# peripheral_PWM.net
KiCad netlist of a schematic drawn in Altium Designer
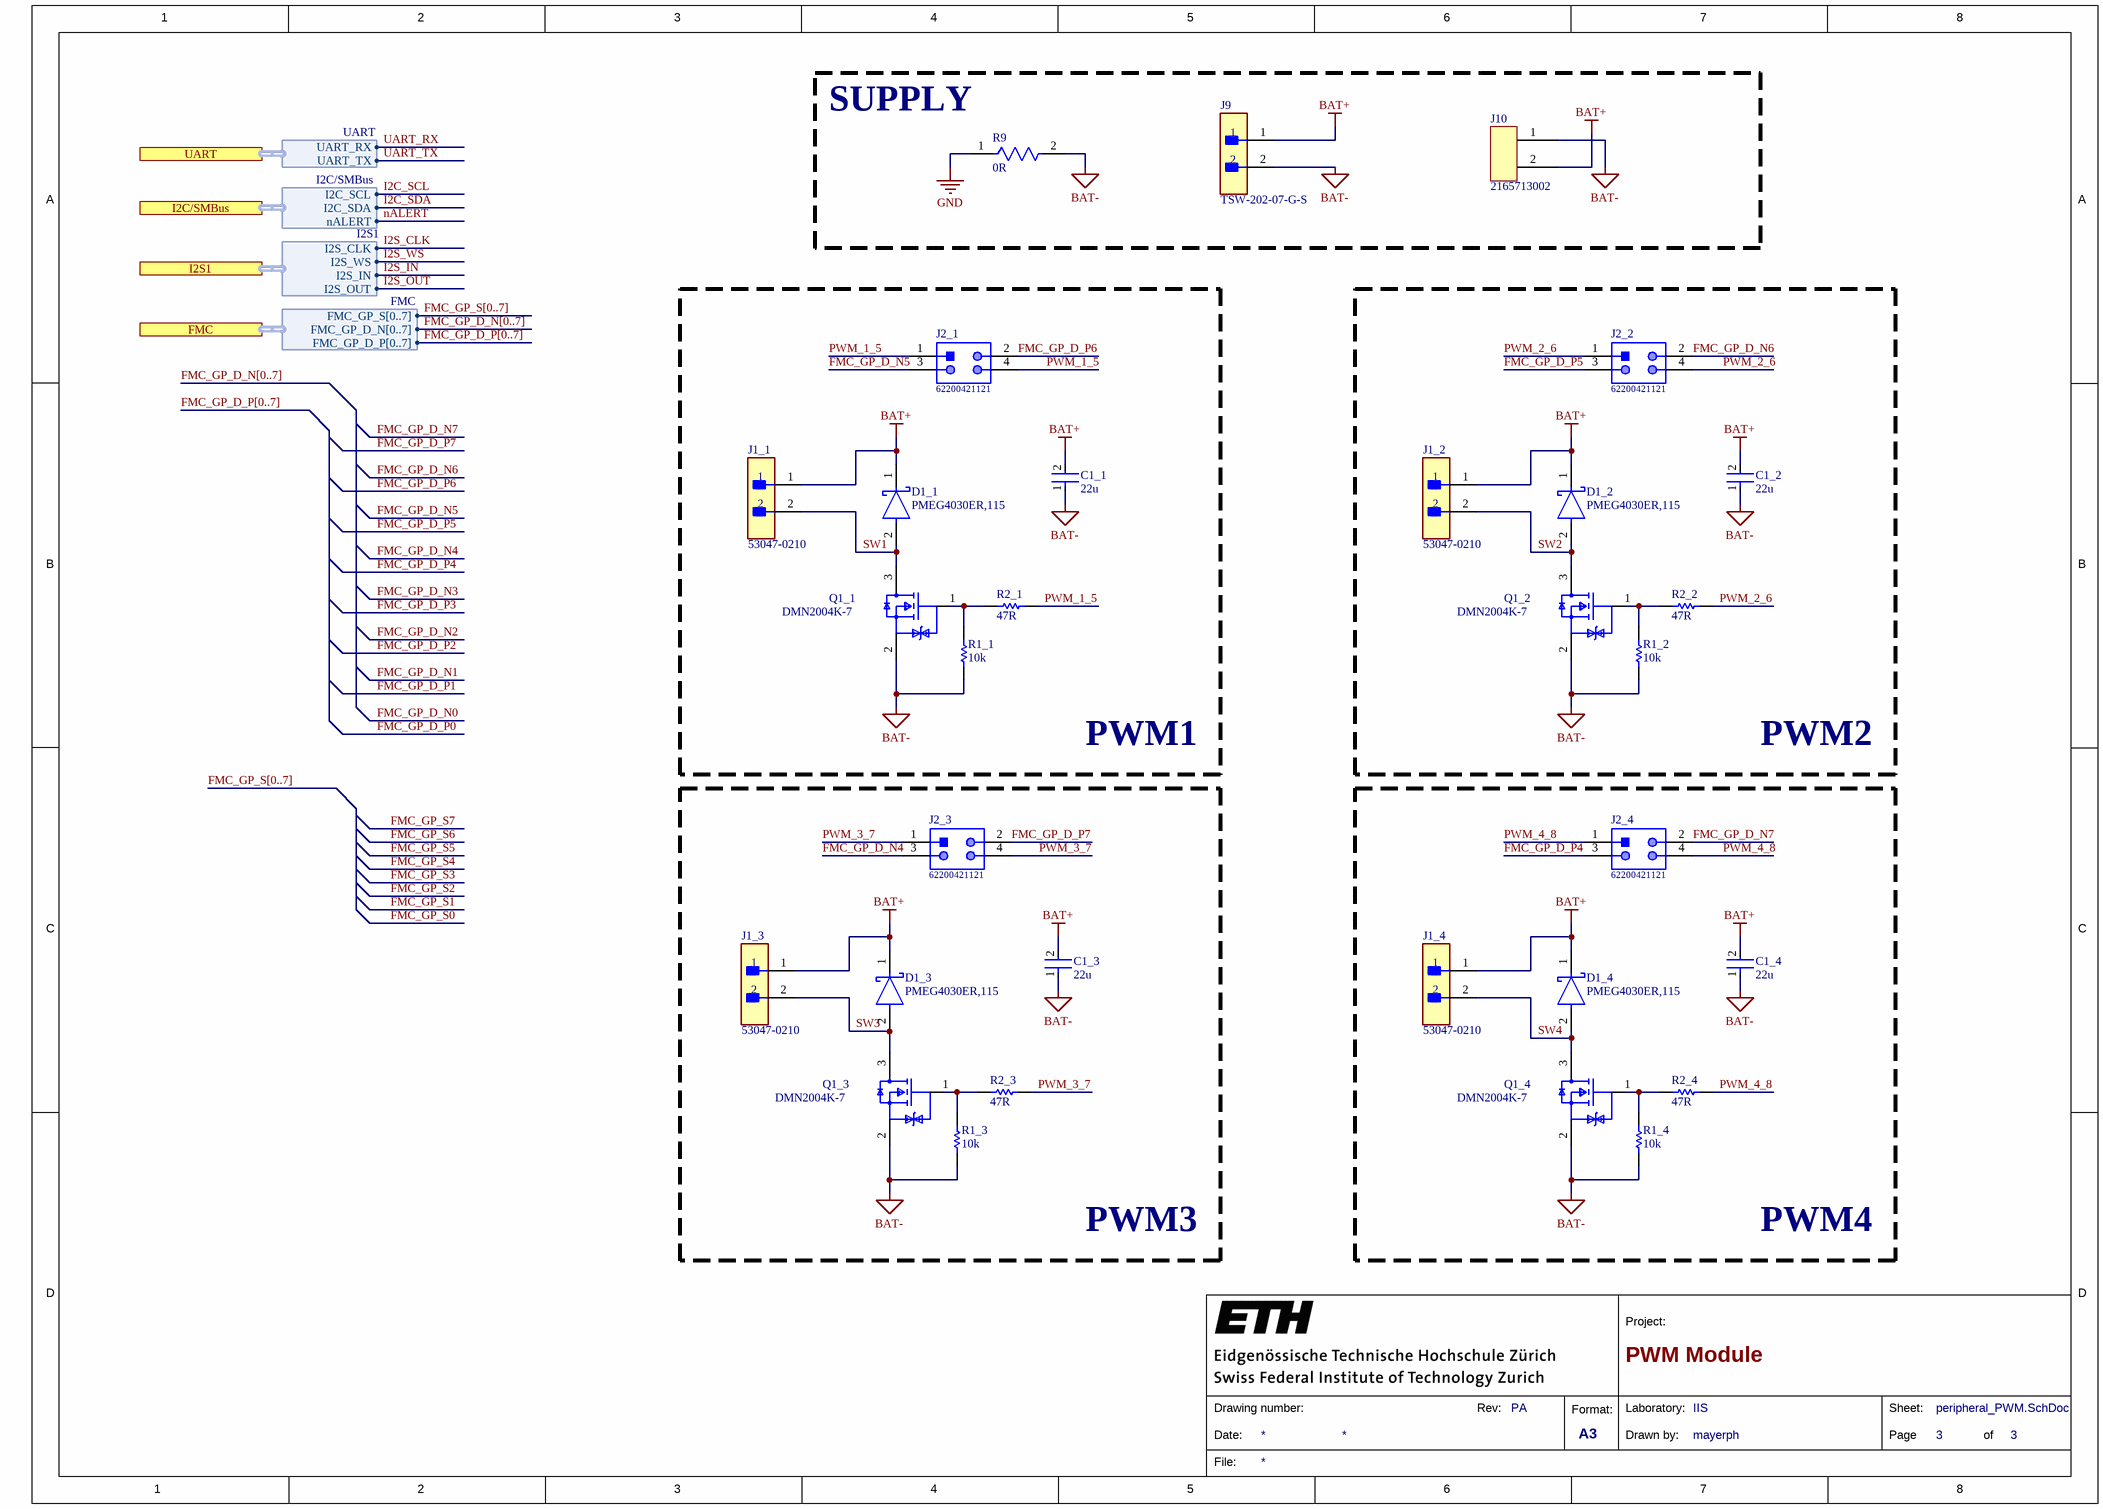
[diagram p0: peripheral_PWM.SchDoc]

(export (version "E")
  (design (tool "Eeschema 10.0.6"))
  (components
    (comp (ref "C1_1")
      (value "22u")
      (footprint "FP-CL10-IPC_B")
      (description "Cap Ceramic 22uF 16V X5R ±20% Pad SMD 0603 +85°C T/R")
      (fields (field (name "TOLERANCE") "20%") (field (name "MANUFACTURER") "Samsung"))
      (libsource (lib "Altium Content Vault") (part "b4654b650e69147ec39a6b967a45e02"))
    )
    (comp (ref "C1_2")
      (value "22u")
      (footprint "FP-CL10-IPC_B")
      (description "Cap Ceramic 22uF 16V X5R ±20% Pad SMD 0603 +85°C T/R")
      (fields (field (name "TOLERANCE") "20%") (field (name "MANUFACTURER") "Samsung"))
      (libsource (lib "Altium Content Vault") (part "b4654b650e69147ec39a6b967a45e02"))
    )
    (comp (ref "C1_3")
      (value "22u")
      (footprint "FP-CL10-IPC_B")
      (description "Cap Ceramic 22uF 16V X5R ±20% Pad SMD 0603 +85°C T/R")
      (fields (field (name "TOLERANCE") "20%") (field (name "MANUFACTURER") "Samsung"))
      (libsource (lib "Altium Content Vault") (part "b4654b650e69147ec39a6b967a45e02"))
    )
    (comp (ref "C1_4")
      (value "22u")
      (footprint "FP-CL10-IPC_B")
      (description "Cap Ceramic 22uF 16V X5R ±20% Pad SMD 0603 +85°C T/R")
      (fields (field (name "TOLERANCE") "20%") (field (name "MANUFACTURER") "Samsung"))
      (libsource (lib "Altium Content Vault") (part "b4654b650e69147ec39a6b967a45e02"))
    )
    (comp (ref "D1_1")
      (value "PMEG4030ER,115")
      (footprint "FP-SOD123W-MFG")
      (description "DIODE SCHOTTKY 40V 3A SOD123W")
      (fields (field (name "MANUFACTURER") "Nexperia USA Inc."))
      (libsource (lib "Altium Content Vault") (part "e9b750318ede8d9850c058872da20e7"))
    )
    (comp (ref "D1_2")
      (value "PMEG4030ER,115")
      (footprint "FP-SOD123W-MFG")
      (description "DIODE SCHOTTKY 40V 3A SOD123W")
      (fields (field (name "MANUFACTURER") "Nexperia USA Inc."))
      (libsource (lib "Altium Content Vault") (part "e9b750318ede8d9850c058872da20e7"))
    )
    (comp (ref "D1_3")
      (value "PMEG4030ER,115")
      (footprint "FP-SOD123W-MFG")
      (description "DIODE SCHOTTKY 40V 3A SOD123W")
      (fields (field (name "MANUFACTURER") "Nexperia USA Inc."))
      (libsource (lib "Altium Content Vault") (part "e9b750318ede8d9850c058872da20e7"))
    )
    (comp (ref "D1_4")
      (value "PMEG4030ER,115")
      (footprint "FP-SOD123W-MFG")
      (description "DIODE SCHOTTKY 40V 3A SOD123W")
      (fields (field (name "MANUFACTURER") "Nexperia USA Inc."))
      (libsource (lib "Altium Content Vault") (part "e9b750318ede8d9850c058872da20e7"))
    )
    (comp (ref "J1_1")
      (value "53047-0210")
      (footprint "FP-53047-0210-MFG")
      (description "CONN HEADER VERT 2POS 1.25MM")
      (fields
        (field (name "OCTOPART") "https://octopart.com/53047-0210-molex-276772")
        (field (name "MANUFACTURER") "Molex")
      )
      (libsource (lib "Altium Content Vault") (part "3bc925449376181038e59eaffc5286c"))
    )
    (comp (ref "J1_2")
      (value "53047-0210")
      (footprint "FP-53047-0210-MFG")
      (description "CONN HEADER VERT 2POS 1.25MM")
      (fields
        (field (name "OCTOPART") "https://octopart.com/53047-0210-molex-276772")
        (field (name "MANUFACTURER") "Molex")
      )
      (libsource (lib "Altium Content Vault") (part "3bc925449376181038e59eaffc5286c"))
    )
    (comp (ref "J1_3")
      (value "53047-0210")
      (footprint "FP-53047-0210-MFG")
      (description "CONN HEADER VERT 2POS 1.25MM")
      (fields
        (field (name "OCTOPART") "https://octopart.com/53047-0210-molex-276772")
        (field (name "MANUFACTURER") "Molex")
      )
      (libsource (lib "Altium Content Vault") (part "3bc925449376181038e59eaffc5286c"))
    )
    (comp (ref "J1_4")
      (value "53047-0210")
      (footprint "FP-53047-0210-MFG")
      (description "CONN HEADER VERT 2POS 1.25MM")
      (fields
        (field (name "OCTOPART") "https://octopart.com/53047-0210-molex-276772")
        (field (name "MANUFACTURER") "Molex")
      )
      (libsource (lib "Altium Content Vault") (part "3bc925449376181038e59eaffc5286c"))
    )
    (comp (ref "J2_1")
      (value "62200421121")
      (footprint "62200421121")
      (description "THT Vertical Pin Header WR-PHD, Pitch 1.27 mm, Dual Row, 4 pins")
      (fields (field (name "MANUFACTURER") "Wurth Elektronik") (field (name "PUBLISHER") "WurthElektronik"))
      (libsource (lib "Altium Content Vault") (part "WE-CN-2P-M-R4"))
    )
    (comp (ref "J2_2")
      (value "62200421121")
      (footprint "62200421121")
      (description "THT Vertical Pin Header WR-PHD, Pitch 1.27 mm, Dual Row, 4 pins")
      (fields (field (name "MANUFACTURER") "Wurth Elektronik") (field (name "PUBLISHER") "WurthElektronik"))
      (libsource (lib "Altium Content Vault") (part "WE-CN-2P-M-R4"))
    )
    (comp (ref "J2_3")
      (value "62200421121")
      (footprint "62200421121")
      (description "THT Vertical Pin Header WR-PHD, Pitch 1.27 mm, Dual Row, 4 pins")
      (fields (field (name "MANUFACTURER") "Wurth Elektronik") (field (name "PUBLISHER") "WurthElektronik"))
      (libsource (lib "Altium Content Vault") (part "WE-CN-2P-M-R4"))
    )
    (comp (ref "J2_4")
      (value "62200421121")
      (footprint "62200421121")
      (description "THT Vertical Pin Header WR-PHD, Pitch 1.27 mm, Dual Row, 4 pins")
      (fields (field (name "MANUFACTURER") "Wurth Elektronik") (field (name "PUBLISHER") "WurthElektronik"))
      (libsource (lib "Altium Content Vault") (part "WE-CN-2P-M-R4"))
    )
    (comp (ref "J9")
      (value "TSW-202-07-G-S")
      (footprint "FP-TSW-202-07-G-S-MFG")
      (description "CONN HEADER VERT 2POS 5.08MM")
      (fields
        (field (name "MANUFACTURER") "Samtec")
        (field (name "OCTOPART") "https://octopart.com/tsw-202-07-g-s-samtec-13117432")
      )
      (libsource (lib "Altium Content Vault") (part "3bc925449376181038e59eaffc5286c"))
    )
    (comp (ref "J10")
      (value "2165713002")
      (footprint "PcbLib1:PCBComponent_1")
      (fields (field (name "MANUFACTURER") "Molex"))
      (libsource (lib "Schlib1") (part "2165713002"))
    )
    (comp (ref "Q1_1")
      (value "DMN2004K-7")
      (footprint "FP-SOT23-MFG")
      (description "MOSFET N-CH 20V 0.63A SOT23-3")
      (fields
        (field (name "OCTOPART") "https://octopart.com/dmn2004k-7-diodes+inc.-7127688")
        (field (name "MANUFACTURER") "Diodes Inc.")
      )
      (libsource (lib "Altium Content Vault") (part "6bf9a98fc5d989e2cd7172508213873"))
    )
    (comp (ref "Q1_2")
      (value "DMN2004K-7")
      (footprint "FP-SOT23-MFG")
      (description "MOSFET N-CH 20V 0.63A SOT23-3")
      (fields
        (field (name "OCTOPART") "https://octopart.com/dmn2004k-7-diodes+inc.-7127688")
        (field (name "MANUFACTURER") "Diodes Inc.")
      )
      (libsource (lib "Altium Content Vault") (part "6bf9a98fc5d989e2cd7172508213873"))
    )
    (comp (ref "Q1_3")
      (value "DMN2004K-7")
      (footprint "FP-SOT23-MFG")
      (description "MOSFET N-CH 20V 0.63A SOT23-3")
      (fields
        (field (name "OCTOPART") "https://octopart.com/dmn2004k-7-diodes+inc.-7127688")
        (field (name "MANUFACTURER") "Diodes Inc.")
      )
      (libsource (lib "Altium Content Vault") (part "6bf9a98fc5d989e2cd7172508213873"))
    )
    (comp (ref "Q1_4")
      (value "DMN2004K-7")
      (footprint "FP-SOT23-MFG")
      (description "MOSFET N-CH 20V 0.63A SOT23-3")
      (fields
        (field (name "OCTOPART") "https://octopart.com/dmn2004k-7-diodes+inc.-7127688")
        (field (name "MANUFACTURER") "Diodes Inc.")
      )
      (libsource (lib "Altium Content Vault") (part "6bf9a98fc5d989e2cd7172508213873"))
    )
    (comp (ref "R1_1")
      (value "10k")
      (footprint "RESC1609X55X30LL15T15")
      (description "Chip Resistor, 10 KOhm, +/- 1%, 0.1 W, -55 to 155 degC, 0603 (1608 Metric), RoHS, Tape and Reel")
      (fields (field (name "TOLERANCE") "1%") (field (name "MANUFACTURER") "Panasonic"))
      (libsource (lib "Altium Content Vault") (part "RES-2"))
    )
    (comp (ref "R1_2")
      (value "10k")
      (footprint "RESC1609X55X30LL15T15")
      (description "Chip Resistor, 10 KOhm, +/- 1%, 0.1 W, -55 to 155 degC, 0603 (1608 Metric), RoHS, Tape and Reel")
      (fields (field (name "TOLERANCE") "1%") (field (name "MANUFACTURER") "Panasonic"))
      (libsource (lib "Altium Content Vault") (part "RES-2"))
    )
    (comp (ref "R1_3")
      (value "10k")
      (footprint "RESC1609X55X30LL15T15")
      (description "Chip Resistor, 10 KOhm, +/- 1%, 0.1 W, -55 to 155 degC, 0603 (1608 Metric), RoHS, Tape and Reel")
      (fields (field (name "TOLERANCE") "1%") (field (name "MANUFACTURER") "Panasonic"))
      (libsource (lib "Altium Content Vault") (part "RES-2"))
    )
    (comp (ref "R1_4")
      (value "10k")
      (footprint "RESC1609X55X30LL15T15")
      (description "Chip Resistor, 10 KOhm, +/- 1%, 0.1 W, -55 to 155 degC, 0603 (1608 Metric), RoHS, Tape and Reel")
      (fields (field (name "TOLERANCE") "1%") (field (name "MANUFACTURER") "Panasonic"))
      (libsource (lib "Altium Content Vault") (part "RES-2"))
    )
    (comp (ref "R2_1")
      (value "47R")
      (footprint "RESC1608X55X30NL15T15")
      (description "Chip Resistor, 47 Ohm, +/- 1%, 0.1 W, -55 to 155 degC, 0603 (1608 Metric), RoHS, Tape and Reel")
      (fields (field (name "TOLERANCE") "1%") (field (name "MANUFACTURER") "Panasonic"))
      (libsource (lib "Altium Content Vault") (part "RES-2"))
    )
    (comp (ref "R2_2")
      (value "47R")
      (footprint "RESC1608X55X30NL15T15")
      (description "Chip Resistor, 47 Ohm, +/- 1%, 0.1 W, -55 to 155 degC, 0603 (1608 Metric), RoHS, Tape and Reel")
      (fields (field (name "TOLERANCE") "1%") (field (name "MANUFACTURER") "Panasonic"))
      (libsource (lib "Altium Content Vault") (part "RES-2"))
    )
    (comp (ref "R2_3")
      (value "47R")
      (footprint "RESC1608X55X30NL15T15")
      (description "Chip Resistor, 47 Ohm, +/- 1%, 0.1 W, -55 to 155 degC, 0603 (1608 Metric), RoHS, Tape and Reel")
      (fields (field (name "TOLERANCE") "1%") (field (name "MANUFACTURER") "Panasonic"))
      (libsource (lib "Altium Content Vault") (part "RES-2"))
    )
    (comp (ref "R2_4")
      (value "47R")
      (footprint "RESC1608X55X30NL15T15")
      (description "Chip Resistor, 47 Ohm, +/- 1%, 0.1 W, -55 to 155 degC, 0603 (1608 Metric), RoHS, Tape and Reel")
      (fields (field (name "TOLERANCE") "1%") (field (name "MANUFACTURER") "Panasonic"))
      (libsource (lib "Altium Content Vault") (part "RES-2"))
    )
    (comp (ref "R9")
      (value "0R")
      (footprint "FP-ERJ-3GEY0R00V-MFG")
      (description "RES SMD 0 OHM JUMPER 1/10W 0603")
      (fields (field (name "TOLERANCE") "5%") (field (name "MANUFACTURER PART NUMBER") "ERJ-3GEY0R00V"))
      (libsource (lib "Altium Content Vault") (part "1029c3af85768c4190bb7ad29bc67b5"))
    )
  )
  (nets
    (net (code "9") (name "/FMC_GP_D_N4") (class "Default")
      (node (ref "J2_3") (pin "3") (pinfunction "3_3") (pintype "passive"))
    )
    (net (code "10") (name "/FMC_GP_D_N5") (class "Default")
      (node (ref "J2_1") (pin "3") (pinfunction "3_3") (pintype "passive"))
    )
    (net (code "11") (name "/FMC_GP_D_N6") (class "Default")
      (node (ref "J2_2") (pin "2") (pinfunction "2_2") (pintype "passive"))
    )
    (net (code "12") (name "/FMC_GP_D_N7") (class "Default")
      (node (ref "J2_4") (pin "2") (pinfunction "2_2") (pintype "passive"))
    )
    (net (code "18") (name "/FMC_GP_D_P4") (class "Default")
      (node (ref "J2_4") (pin "3") (pinfunction "3_3") (pintype "passive"))
    )
    (net (code "19") (name "/FMC_GP_D_P5") (class "Default")
      (node (ref "J2_2") (pin "3") (pinfunction "3_3") (pintype "passive"))
    )
    (net (code "20") (name "/FMC_GP_D_P6") (class "Default")
      (node (ref "J2_1") (pin "2") (pinfunction "2_2") (pintype "passive"))
    )
    (net (code "21") (name "/FMC_GP_D_P7") (class "Default")
      (node (ref "J2_3") (pin "2") (pinfunction "2_2") (pintype "passive"))
    )
    (net (code "38") (name "/PWM_1_5") (class "Default")
      (node (ref "J2_1") (pin "1") (pinfunction "1_1") (pintype "passive"))
      (node (ref "J2_1") (pin "4") (pinfunction "4_4") (pintype "passive"))
      (node (ref "R2_1") (pin "2") (pinfunction "2_2") (pintype "passive"))
    )
    (net (code "39") (name "/PWM_2_6") (class "Default")
      (node (ref "J2_2") (pin "1") (pinfunction "1_1") (pintype "passive"))
      (node (ref "J2_2") (pin "4") (pinfunction "4_4") (pintype "passive"))
      (node (ref "R2_2") (pin "2") (pinfunction "2_2") (pintype "passive"))
    )
    (net (code "40") (name "/PWM_3_7") (class "Default")
      (node (ref "J2_3") (pin "1") (pinfunction "1_1") (pintype "passive"))
      (node (ref "J2_3") (pin "4") (pinfunction "4_4") (pintype "passive"))
      (node (ref "R2_3") (pin "2") (pinfunction "2_2") (pintype "passive"))
    )
    (net (code "41") (name "/PWM_4_8") (class "Default")
      (node (ref "J2_4") (pin "1") (pinfunction "1_1") (pintype "passive"))
      (node (ref "J2_4") (pin "4") (pinfunction "4_4") (pintype "passive"))
      (node (ref "R2_4") (pin "2") (pinfunction "2_2") (pintype "passive"))
    )
    (net (code "42") (name "/SW1") (class "Default")
      (node (ref "D1_1") (pin "2") (pinfunction "A_2") (pintype "passive"))
      (node (ref "J1_1") (pin "2") (pinfunction "2_2") (pintype "passive"))
      (node (ref "Q1_1") (pin "3") (pinfunction "D_3") (pintype "passive"))
    )
    (net (code "43") (name "/SW2") (class "Default")
      (node (ref "D1_2") (pin "2") (pinfunction "A_2") (pintype "passive"))
      (node (ref "J1_2") (pin "2") (pinfunction "2_2") (pintype "passive"))
      (node (ref "Q1_2") (pin "3") (pinfunction "D_3") (pintype "passive"))
    )
    (net (code "44") (name "/SW3") (class "Default")
      (node (ref "D1_3") (pin "2") (pinfunction "A_2") (pintype "passive"))
      (node (ref "J1_3") (pin "2") (pinfunction "2_2") (pintype "passive"))
      (node (ref "Q1_3") (pin "3") (pinfunction "D_3") (pintype "passive"))
    )
    (net (code "45") (name "/SW4") (class "Default")
      (node (ref "D1_4") (pin "2") (pinfunction "A_2") (pintype "passive"))
      (node (ref "J1_4") (pin "2") (pinfunction "2_2") (pintype "passive"))
      (node (ref "Q1_4") (pin "3") (pinfunction "D_3") (pintype "passive"))
    )
    (net (code "53") (name "BAT+") (class "Default")
      (node (ref "C1_1") (pin "2") (pinfunction "2_2") (pintype "passive"))
      (node (ref "C1_2") (pin "2") (pinfunction "2_2") (pintype "passive"))
      (node (ref "C1_3") (pin "2") (pinfunction "2_2") (pintype "passive"))
      (node (ref "C1_4") (pin "2") (pinfunction "2_2") (pintype "passive"))
      (node (ref "D1_1") (pin "1") (pinfunction "C_1") (pintype "passive"))
      (node (ref "D1_2") (pin "1") (pinfunction "C_1") (pintype "passive"))
      (node (ref "D1_3") (pin "1") (pinfunction "C_1") (pintype "passive"))
      (node (ref "D1_4") (pin "1") (pinfunction "C_1") (pintype "passive"))
      (node (ref "J10") (pin "2") (pintype "passive"))
      (node (ref "J1_1") (pin "1") (pinfunction "1_1") (pintype "passive"))
      (node (ref "J1_2") (pin "1") (pinfunction "1_1") (pintype "passive"))
      (node (ref "J1_3") (pin "1") (pinfunction "1_1") (pintype "passive"))
      (node (ref "J1_4") (pin "1") (pinfunction "1_1") (pintype "passive"))
      (node (ref "J9") (pin "1") (pinfunction "1_1") (pintype "passive"))
    )
    (net (code "54") (name "BAT-") (class "Default")
      (node (ref "C1_1") (pin "1") (pinfunction "1_1") (pintype "passive"))
      (node (ref "C1_2") (pin "1") (pinfunction "1_1") (pintype "passive"))
      (node (ref "C1_3") (pin "1") (pinfunction "1_1") (pintype "passive"))
      (node (ref "C1_4") (pin "1") (pinfunction "1_1") (pintype "passive"))
      (node (ref "J10") (pin "1") (pintype "passive"))
      (node (ref "J9") (pin "2") (pinfunction "2_2") (pintype "passive"))
      (node (ref "Q1_1") (pin "2") (pinfunction "S_2") (pintype "passive"))
      (node (ref "Q1_2") (pin "2") (pinfunction "S_2") (pintype "passive"))
      (node (ref "Q1_3") (pin "2") (pinfunction "S_2") (pintype "passive"))
      (node (ref "Q1_4") (pin "2") (pinfunction "S_2") (pintype "passive"))
      (node (ref "R1_1") (pin "1") (pinfunction "1_1") (pintype "passive"))
      (node (ref "R1_2") (pin "1") (pinfunction "1_1") (pintype "passive"))
      (node (ref "R1_3") (pin "1") (pinfunction "1_1") (pintype "passive"))
      (node (ref "R1_4") (pin "1") (pinfunction "1_1") (pintype "passive"))
      (node (ref "R9") (pin "2") (pinfunction "2_2") (pintype "passive"))
    )
    (net (code "55") (name "GND") (class "Default")
      (node (ref "R9") (pin "1") (pinfunction "1_1") (pintype "passive"))
    )
    (net (code "56") (name "Net-(Q1_1-G)") (class "Default")
      (node (ref "Q1_1") (pin "1") (pinfunction "G_1") (pintype "passive"))
      (node (ref "R1_1") (pin "2") (pinfunction "2_2") (pintype "passive"))
      (node (ref "R2_1") (pin "1") (pinfunction "1_1") (pintype "passive"))
    )
    (net (code "57") (name "Net-(Q1_2-G)") (class "Default")
      (node (ref "Q1_2") (pin "1") (pinfunction "G_1") (pintype "passive"))
      (node (ref "R1_2") (pin "2") (pinfunction "2_2") (pintype "passive"))
      (node (ref "R2_2") (pin "1") (pinfunction "1_1") (pintype "passive"))
    )
    (net (code "58") (name "Net-(Q1_3-G)") (class "Default")
      (node (ref "Q1_3") (pin "1") (pinfunction "G_1") (pintype "passive"))
      (node (ref "R1_3") (pin "2") (pinfunction "2_2") (pintype "passive"))
      (node (ref "R2_3") (pin "1") (pinfunction "1_1") (pintype "passive"))
    )
    (net (code "59") (name "Net-(Q1_4-G)") (class "Default")
      (node (ref "Q1_4") (pin "1") (pinfunction "G_1") (pintype "passive"))
      (node (ref "R1_4") (pin "2") (pinfunction "2_2") (pintype "passive"))
      (node (ref "R2_4") (pin "1") (pinfunction "1_1") (pintype "passive"))
    )
  )
)
